# Relay_Board.net
KiCad netlist of a schematic drawn in EAGLE
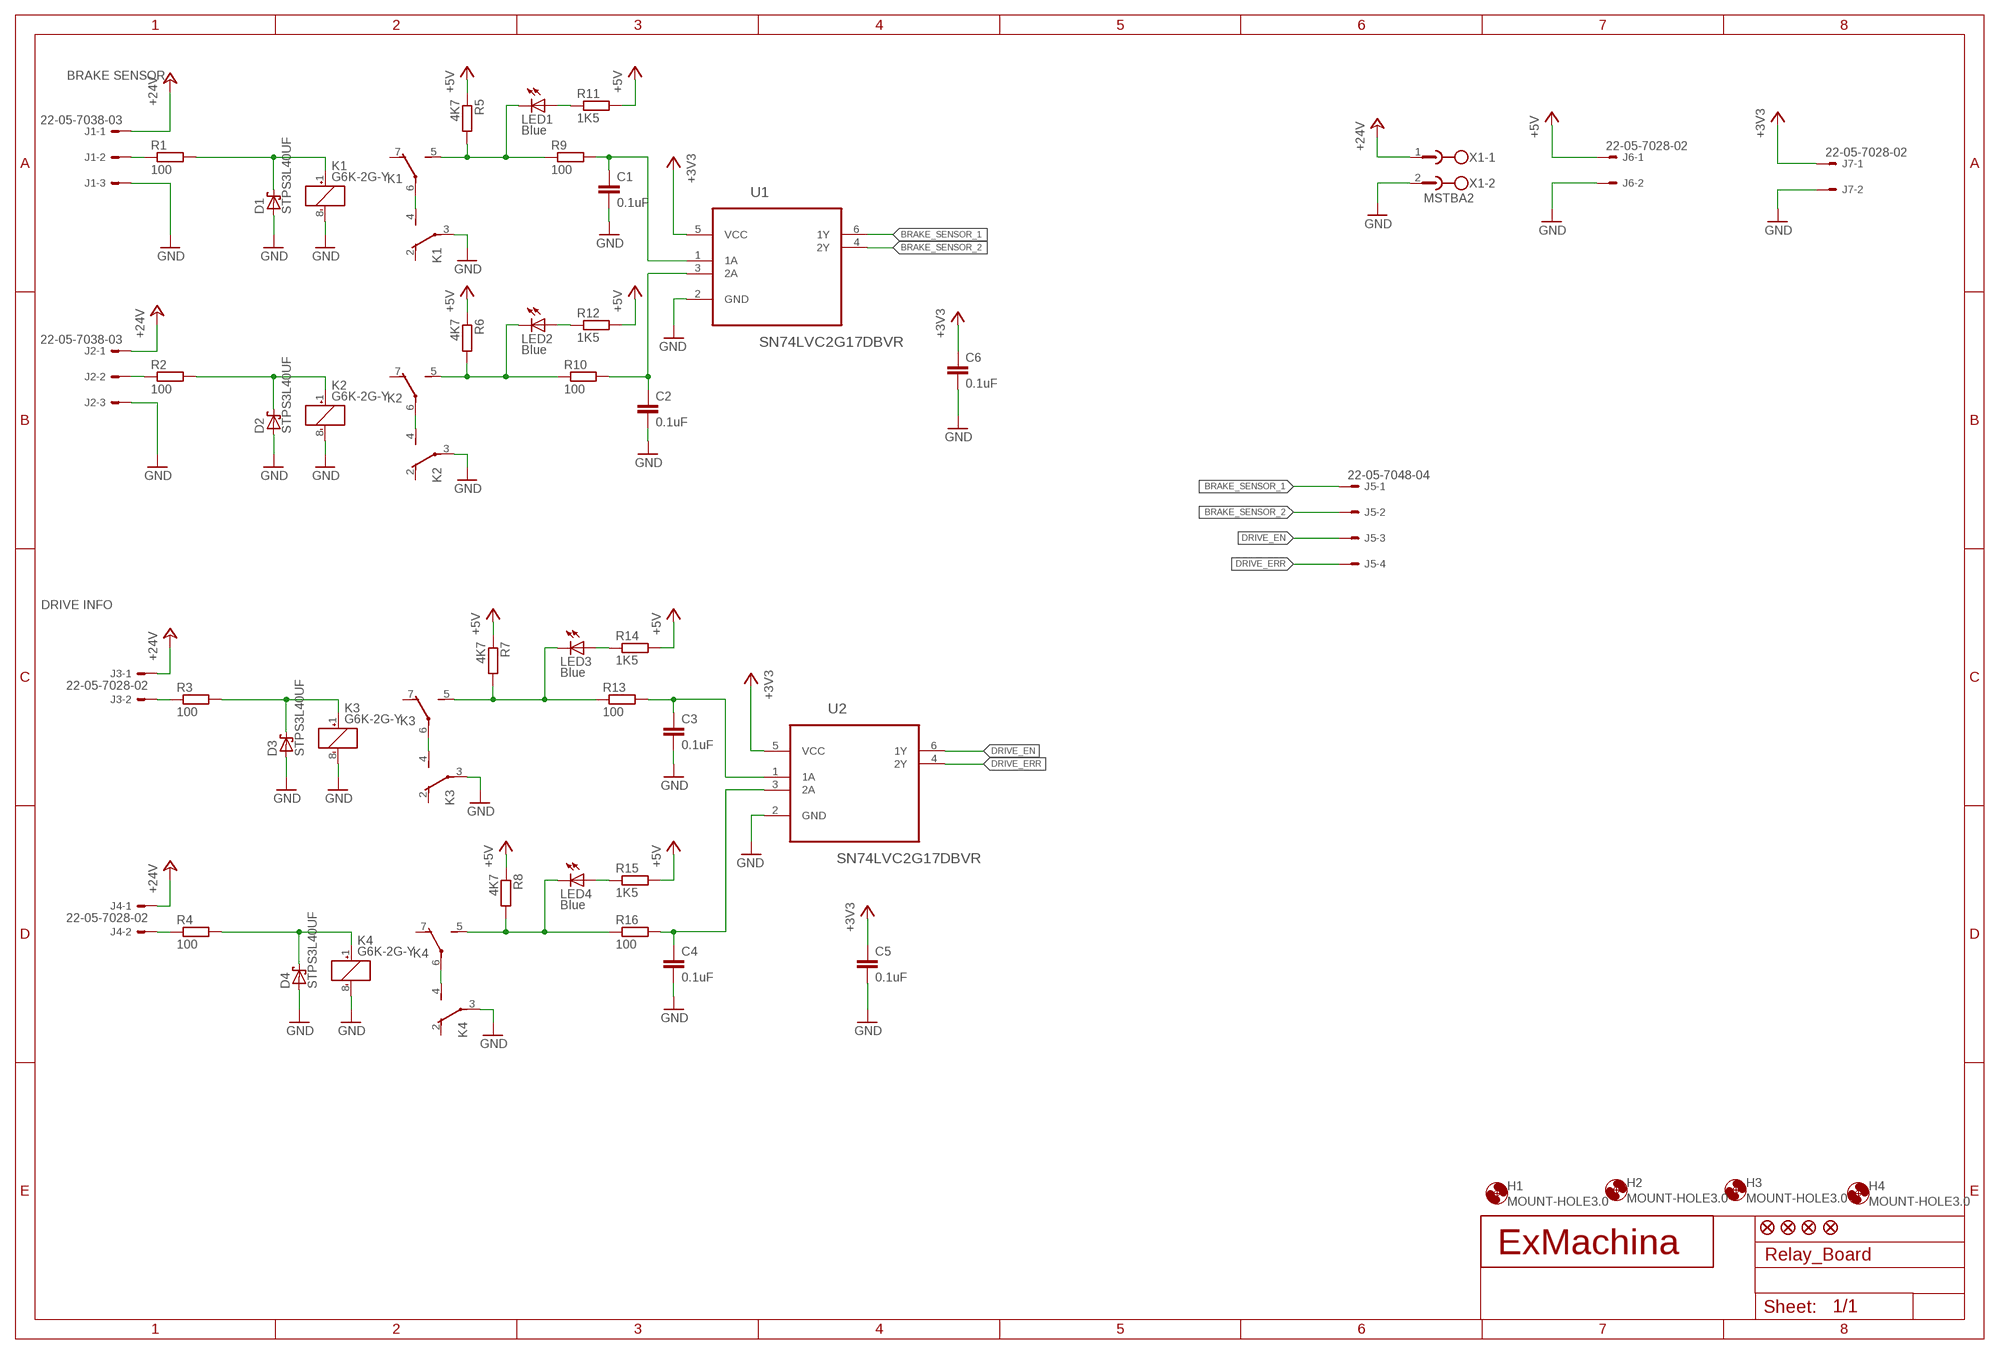
[diagram p0: schematic, sheet 1]

(export (version "E")
  (design (tool "Eeschema 10.0.6"))
  (components
    (comp (ref "C1")
      (value "0.1uF")
      (footprint "eagle-import:C0603")
      (fields (field (name "MPN") "MC0603B104K250CT"))
      (libsource (lib "eagle-import") (part "C-EUC0603"))
    )
    (comp (ref "C2")
      (value "0.1uF")
      (footprint "eagle-import:C0603")
      (fields (field (name "MPN") "MC0603B104K250CT"))
      (libsource (lib "eagle-import") (part "C-EUC0603"))
    )
    (comp (ref "C3")
      (value "0.1uF")
      (footprint "eagle-import:C0603")
      (fields (field (name "MPN") "MC0603B104K250CT"))
      (libsource (lib "eagle-import") (part "C-EUC0603"))
    )
    (comp (ref "C4")
      (value "0.1uF")
      (footprint "eagle-import:C0603")
      (fields (field (name "MPN") "MC0603B104K250CT"))
      (libsource (lib "eagle-import") (part "C-EUC0603"))
    )
    (comp (ref "C5")
      (value "0.1uF")
      (footprint "eagle-import:C0603")
      (fields (field (name "MPN") "MC0603B104K250CT"))
      (libsource (lib "eagle-import") (part "C-EUC0603"))
    )
    (comp (ref "C6")
      (value "0.1uF")
      (footprint "eagle-import:C0603")
      (fields (field (name "MPN") "MC0603B104K250CT"))
      (libsource (lib "eagle-import") (part "C-EUC0603"))
    )
    (comp (ref "D1")
      (value "STPS3L40UF")
      (footprint "eagle-import:SMB")
      (fields (field (name "MP") "STMICROELECTRONICS"))
      (libsource (lib "eagle-import") (part "STPS3L40?UF"))
    )
    (comp (ref "D2")
      (value "STPS3L40UF")
      (footprint "eagle-import:SMB")
      (fields (field (name "MP") "STMICROELECTRONICS"))
      (libsource (lib "eagle-import") (part "STPS3L40?UF"))
    )
    (comp (ref "D3")
      (value "STPS3L40UF")
      (footprint "eagle-import:SMB")
      (fields (field (name "MP") "STMICROELECTRONICS"))
      (libsource (lib "eagle-import") (part "STPS3L40?UF"))
    )
    (comp (ref "D4")
      (value "STPS3L40UF")
      (footprint "eagle-import:SMB")
      (fields (field (name "MP") "STMICROELECTRONICS"))
      (libsource (lib "eagle-import") (part "STPS3L40?UF"))
    )
    (comp (ref "H1")
      (value "MOUNT-HOLE3.0")
      (footprint "eagle-import:3,0")
      (libsource (lib "eagle-import") (part "MOUNT-HOLE3.0"))
    )
    (comp (ref "H2")
      (value "MOUNT-HOLE3.0")
      (footprint "eagle-import:3,0")
      (libsource (lib "eagle-import") (part "MOUNT-HOLE3.0"))
    )
    (comp (ref "H3")
      (value "MOUNT-HOLE3.0")
      (footprint "eagle-import:3,0")
      (libsource (lib "eagle-import") (part "MOUNT-HOLE3.0"))
    )
    (comp (ref "H4")
      (value "MOUNT-HOLE3.0")
      (footprint "eagle-import:3,0")
      (libsource (lib "eagle-import") (part "MOUNT-HOLE3.0"))
    )
    (comp (ref "J1")
      (value "22-05-7038-03")
      (footprint "eagle-import:7395-03")
      (fields (field (name "MPN") "22-05-7038") (field (name "OC_NEWARK") "26M6362"))
      (libsource (lib "eagle-import") (part "22-?-0305-7038"))
    )
    (comp (ref "J2")
      (value "22-05-7038-03")
      (footprint "eagle-import:7395-03")
      (fields (field (name "MPN") "22-05-7038") (field (name "OC_NEWARK") "26M6362"))
      (libsource (lib "eagle-import") (part "22-?-0305-7038"))
    )
    (comp (ref "J3")
      (value "22-05-7028-02")
      (footprint "eagle-import:7395-02")
      (fields (field (name "MPN") "22-05-7028") (field (name "OC_NEWARK") "25M1728"))
      (libsource (lib "eagle-import") (part "22-?-0205-7028"))
    )
    (comp (ref "J4")
      (value "22-05-7028-02")
      (footprint "eagle-import:7395-02")
      (fields (field (name "MPN") "22-05-7028") (field (name "OC_NEWARK") "25M1728"))
      (libsource (lib "eagle-import") (part "22-?-0205-7028"))
    )
    (comp (ref "J5")
      (value "22-05-7048-04")
      (footprint "eagle-import:7395-04")
      (fields (field (name "MPN") "22-05-7048") (field (name "OC_NEWARK") "26M6363"))
      (libsource (lib "eagle-import") (part "22-?-0405-7048"))
    )
    (comp (ref "J6")
      (value "22-05-7028-02")
      (footprint "eagle-import:7395-02")
      (fields (field (name "MPN") "22-05-7028") (field (name "OC_NEWARK") "25M1728"))
      (libsource (lib "eagle-import") (part "22-?-0205-7028"))
    )
    (comp (ref "J7")
      (value "22-05-7028-02")
      (footprint "eagle-import:7395-02")
      (fields (field (name "MPN") "22-05-7028") (field (name "OC_NEWARK") "25M1728"))
      (libsource (lib "eagle-import") (part "22-?-0205-7028"))
    )
    (comp (ref "JP1")
      (value "FIDUCIAL1X2")
      (footprint "eagle-import:FIDUCIAL-1X2")
      (libsource (lib "eagle-import") (part "FIDUCIAL1X2"))
    )
    (comp (ref "JP2")
      (value "FIDUCIAL1X2")
      (footprint "eagle-import:FIDUCIAL-1X2")
      (libsource (lib "eagle-import") (part "FIDUCIAL1X2"))
    )
    (comp (ref "JP3")
      (value "FIDUCIAL1X2")
      (footprint "eagle-import:FIDUCIAL-1X2")
      (libsource (lib "eagle-import") (part "FIDUCIAL1X2"))
    )
    (comp (ref "JP4")
      (value "FIDUCIAL1X2")
      (footprint "eagle-import:FIDUCIAL-1X2")
      (libsource (lib "eagle-import") (part "FIDUCIAL1X2"))
    )
    (comp (ref "K1")
      (value "G6K-2G-Y")
      (footprint "eagle-import:G6K-2G-Y")
      (fields (field (name "MPN") "G6K-2G-Y 24DC") (field (name "OC_NEWARK") "82T9378"))
      (libsource (lib "eagle-import") (part "G6K-2G-Y"))
    )
    (comp (ref "K2")
      (value "G6K-2G-Y")
      (footprint "eagle-import:G6K-2G-Y")
      (fields (field (name "MPN") "G6K-2G-Y 24DC") (field (name "OC_NEWARK") "82T9378"))
      (libsource (lib "eagle-import") (part "G6K-2G-Y"))
    )
    (comp (ref "K3")
      (value "G6K-2G-Y")
      (footprint "eagle-import:G6K-2G-Y")
      (fields (field (name "MPN") "G6K-2G-Y 24DC") (field (name "OC_NEWARK") "82T9378"))
      (libsource (lib "eagle-import") (part "G6K-2G-Y"))
    )
    (comp (ref "K4")
      (value "G6K-2G-Y")
      (footprint "eagle-import:G6K-2G-Y")
      (fields (field (name "MPN") "G6K-2G-Y 24DC") (field (name "OC_NEWARK") "82T9378"))
      (libsource (lib "eagle-import") (part "G6K-2G-Y"))
    )
    (comp (ref "LED1")
      (value "Blue")
      (footprint "eagle-import:CHIPLED_0603")
      (fields (field (name "MPN") "OVS-0603"))
      (libsource (lib "eagle-import") (part "LEDCHIPLED_0603"))
    )
    (comp (ref "LED2")
      (value "Blue")
      (footprint "eagle-import:CHIPLED_0603")
      (fields (field (name "MPN") "OVS-0603"))
      (libsource (lib "eagle-import") (part "LEDCHIPLED_0603"))
    )
    (comp (ref "LED3")
      (value "Blue")
      (footprint "eagle-import:CHIPLED_0603")
      (fields (field (name "MPN") "OVS-0603"))
      (libsource (lib "eagle-import") (part "LEDCHIPLED_0603"))
    )
    (comp (ref "LED4")
      (value "Blue")
      (footprint "eagle-import:CHIPLED_0603")
      (fields (field (name "MPN") "OVS-0603"))
      (libsource (lib "eagle-import") (part "LEDCHIPLED_0603"))
    )
    (comp (ref "R1")
      (value "100")
      (footprint "eagle-import:R0603")
      (fields (field (name "MPN") "MCMR06X1000FTL"))
      (libsource (lib "eagle-import") (part "R-EU_R0603"))
    )
    (comp (ref "R2")
      (value "100")
      (footprint "eagle-import:R0603")
      (fields (field (name "MPN") "MCMR06X1000FTL"))
      (libsource (lib "eagle-import") (part "R-EU_R0603"))
    )
    (comp (ref "R3")
      (value "100")
      (footprint "eagle-import:R0603")
      (fields (field (name "MPN") "MCMR06X1000FTL"))
      (libsource (lib "eagle-import") (part "R-EU_R0603"))
    )
    (comp (ref "R4")
      (value "100")
      (footprint "eagle-import:R0603")
      (fields (field (name "MPN") "MCMR06X1000FTL"))
      (libsource (lib "eagle-import") (part "R-EU_R0603"))
    )
    (comp (ref "R5")
      (value "4K7")
      (footprint "eagle-import:R0603")
      (fields (field (name "MPN") "MCMR06X4701FTL"))
      (libsource (lib "eagle-import") (part "R-EU_R0603"))
    )
    (comp (ref "R6")
      (value "4K7")
      (footprint "eagle-import:R0603")
      (fields (field (name "MPN") "MCMR06X4701FTL"))
      (libsource (lib "eagle-import") (part "R-EU_R0603"))
    )
    (comp (ref "R7")
      (value "4K7")
      (footprint "eagle-import:R0603")
      (fields (field (name "MPN") "MCMR06X4701FTL"))
      (libsource (lib "eagle-import") (part "R-EU_R0603"))
    )
    (comp (ref "R8")
      (value "4K7")
      (footprint "eagle-import:R0603")
      (fields (field (name "MPN") "MCMR06X4701FTL"))
      (libsource (lib "eagle-import") (part "R-EU_R0603"))
    )
    (comp (ref "R9")
      (value "100")
      (footprint "eagle-import:R0603")
      (fields (field (name "MPN") "MCMR06X1000FTL"))
      (libsource (lib "eagle-import") (part "R-EU_R0603"))
    )
    (comp (ref "R10")
      (value "100")
      (footprint "eagle-import:R0603")
      (fields (field (name "MPN") "MCMR06X1000FTL"))
      (libsource (lib "eagle-import") (part "R-EU_R0603"))
    )
    (comp (ref "R11")
      (value "1K5")
      (footprint "eagle-import:R0603")
      (fields (field (name "MPN") "MCMR06X1501FTL"))
      (libsource (lib "eagle-import") (part "R-EU_R0603"))
    )
    (comp (ref "R12")
      (value "1K5")
      (footprint "eagle-import:R0603")
      (fields (field (name "MPN") "MCMR06X1501FTL"))
      (libsource (lib "eagle-import") (part "R-EU_R0603"))
    )
    (comp (ref "R13")
      (value "100")
      (footprint "eagle-import:R0603")
      (fields (field (name "MPN") "MCMR06X1000FTL"))
      (libsource (lib "eagle-import") (part "R-EU_R0603"))
    )
    (comp (ref "R14")
      (value "1K5")
      (footprint "eagle-import:R0603")
      (fields (field (name "MPN") "MCMR06X1501FTL"))
      (libsource (lib "eagle-import") (part "R-EU_R0603"))
    )
    (comp (ref "R15")
      (value "1K5")
      (footprint "eagle-import:R0603")
      (fields (field (name "MPN") "MCMR06X1501FTL"))
      (libsource (lib "eagle-import") (part "R-EU_R0603"))
    )
    (comp (ref "R16")
      (value "100")
      (footprint "eagle-import:R0603")
      (fields (field (name "MPN") "MCMR06X1000FTL"))
      (libsource (lib "eagle-import") (part "R-EU_R0603"))
    )
    (comp (ref "T1")
      (value "EXMACHINA-LOGO-NAME")
      (footprint "eagle-import:EXM-LOGO-BASELINE")
      (libsource (lib "eagle-import") (part "EXMACHINA-LOGO-NAME"))
    )
    (comp (ref "U1")
      (value "SN74LVC2G17DBVR")
      (footprint "eagle-import:SOT95P280X145-6N")
      (fields (field (name "MF") "TEXAS INSTRUMENTS"))
      (libsource (lib "eagle-import") (part "SN74LVC2G17DBVR"))
    )
    (comp (ref "U2")
      (value "SN74LVC2G17DBVR")
      (footprint "eagle-import:SOT95P280X145-6N")
      (fields (field (name "MF") "TEXAS INSTRUMENTS"))
      (libsource (lib "eagle-import") (part "SN74LVC2G17DBVR"))
    )
    (comp (ref "X1")
      (value "MSTBA2")
      (footprint "eagle-import:MSTBA2")
      (fields (field (name "MF") "FARNELL") (field (name "MPN") "1757242"))
      (libsource (lib "eagle-import") (part "MSTBA2"))
    )
  )
  (nets
    (net (code "1") (name "+3V3") (class "Default")
      (node (ref "C5") (pin "1") (pinfunction "1_1") (pintype "passive"))
      (node (ref "C6") (pin "1") (pinfunction "1_1") (pintype "passive"))
      (node (ref "J7") (pin "1") (pinfunction "S_1") (pintype "passive"))
      (node (ref "U1") (pin "5") (pinfunction "VCC_5") (pintype "power_in"))
      (node (ref "U2") (pin "5") (pinfunction "VCC_5") (pintype "power_in"))
    )
    (net (code "2") (name "+5V") (class "Default")
      (node (ref "J6") (pin "1") (pinfunction "S_1") (pintype "passive"))
      (node (ref "R11") (pin "2") (pinfunction "2_2") (pintype "passive"))
      (node (ref "R12") (pin "2") (pinfunction "2_2") (pintype "passive"))
      (node (ref "R14") (pin "2") (pinfunction "2_2") (pintype "passive"))
      (node (ref "R15") (pin "2") (pinfunction "2_2") (pintype "passive"))
      (node (ref "R5") (pin "1") (pinfunction "1_1") (pintype "passive"))
      (node (ref "R6") (pin "1") (pinfunction "1_1") (pintype "passive"))
      (node (ref "R7") (pin "1") (pinfunction "1_1") (pintype "passive"))
      (node (ref "R8") (pin "1") (pinfunction "1_1") (pintype "passive"))
    )
    (net (code "3") (name "+24V") (class "Default")
      (node (ref "J1") (pin "1") (pinfunction "S_1") (pintype "passive"))
      (node (ref "J2") (pin "1") (pinfunction "S_1") (pintype "passive"))
      (node (ref "J3") (pin "1") (pinfunction "S_1") (pintype "passive"))
      (node (ref "J4") (pin "1") (pinfunction "S_1") (pintype "passive"))
      (node (ref "X1") (pin "1") (pinfunction "1_1") (pintype "passive"))
    )
    (net (code "4") (name "BRAKE_SENSOR_1") (class "Default")
      (node (ref "J5") (pin "1") (pinfunction "S_1") (pintype "passive"))
      (node (ref "U1") (pin "6") (pinfunction "1Y_6") (pintype "output"))
    )
    (net (code "5") (name "BRAKE_SENSOR_2") (class "Default")
      (node (ref "J5") (pin "2") (pinfunction "S_2") (pintype "passive"))
      (node (ref "U1") (pin "4") (pinfunction "2Y_4") (pintype "output"))
    )
    (net (code "6") (name "DRIVE_EN") (class "Default")
      (node (ref "J5") (pin "3") (pinfunction "S_3") (pintype "passive"))
      (node (ref "U2") (pin "6") (pinfunction "1Y_6") (pintype "output"))
    )
    (net (code "7") (name "DRIVE_ERR") (class "Default")
      (node (ref "J5") (pin "4") (pinfunction "S_4") (pintype "passive"))
      (node (ref "U2") (pin "4") (pinfunction "2Y_4") (pintype "output"))
    )
    (net (code "8") (name "GND") (class "Default")
      (node (ref "C1") (pin "2") (pinfunction "2_2") (pintype "passive"))
      (node (ref "C2") (pin "2") (pinfunction "2_2") (pintype "passive"))
      (node (ref "C3") (pin "2") (pinfunction "2_2") (pintype "passive"))
      (node (ref "C4") (pin "2") (pinfunction "2_2") (pintype "passive"))
      (node (ref "C5") (pin "2") (pinfunction "2_2") (pintype "passive"))
      (node (ref "C6") (pin "2") (pinfunction "2_2") (pintype "passive"))
      (node (ref "D1") (pin "A") (pinfunction "A_A") (pintype "passive"))
      (node (ref "D2") (pin "A") (pinfunction "A_A") (pintype "passive"))
      (node (ref "D3") (pin "A") (pinfunction "A_A") (pintype "passive"))
      (node (ref "D4") (pin "A") (pinfunction "A_A") (pintype "passive"))
      (node (ref "J1") (pin "3") (pinfunction "S_3") (pintype "passive"))
      (node (ref "J2") (pin "3") (pinfunction "S_3") (pintype "passive"))
      (node (ref "J6") (pin "2") (pinfunction "S_2") (pintype "passive"))
      (node (ref "J7") (pin "2") (pinfunction "S_2") (pintype "passive"))
      (node (ref "K1") (pin "3") (pinfunction "P_3") (pintype "passive"))
      (node (ref "K1") (pin "8") (pinfunction "-_8") (pintype "passive"))
      (node (ref "K2") (pin "3") (pinfunction "P_3") (pintype "passive"))
      (node (ref "K2") (pin "8") (pinfunction "-_8") (pintype "passive"))
      (node (ref "K3") (pin "3") (pinfunction "P_3") (pintype "passive"))
      (node (ref "K3") (pin "8") (pinfunction "-_8") (pintype "passive"))
      (node (ref "K4") (pin "3") (pinfunction "P_3") (pintype "passive"))
      (node (ref "K4") (pin "8") (pinfunction "-_8") (pintype "passive"))
      (node (ref "U1") (pin "2") (pinfunction "GND_2") (pintype "passive"))
      (node (ref "U2") (pin "2") (pinfunction "GND_2") (pintype "passive"))
      (node (ref "X1") (pin "2") (pinfunction "1_2") (pintype "passive"))
    )
    (net (code "9") (name "Net-(J1B-S)") (class "Default")
      (node (ref "J1") (pin "2") (pinfunction "S_2") (pintype "passive"))
      (node (ref "R1") (pin "1") (pinfunction "1_1") (pintype "passive"))
    )
    (net (code "10") (name "Net-(J2B-S)") (class "Default")
      (node (ref "J2") (pin "2") (pinfunction "S_2") (pintype "passive"))
      (node (ref "R2") (pin "1") (pinfunction "1_1") (pintype "passive"))
    )
    (net (code "11") (name "Net-(J3B-S)") (class "Default")
      (node (ref "J3") (pin "2") (pinfunction "S_2") (pintype "passive"))
      (node (ref "R3") (pin "1") (pinfunction "1_1") (pintype "passive"))
    )
    (net (code "12") (name "Net-(J4B-S)") (class "Default")
      (node (ref "J4") (pin "2") (pinfunction "S_2") (pintype "passive"))
      (node (ref "R4") (pin "1") (pinfunction "1_1") (pintype "passive"))
    )
    (net (code "13") (name "Net-(K1A-+)") (class "Default")
      (node (ref "D1") (pin "C") (pinfunction "C_C") (pintype "passive"))
      (node (ref "K1") (pin "1") (pinfunction "+_1") (pintype "passive"))
      (node (ref "R1") (pin "2") (pinfunction "2_2") (pintype "passive"))
    )
    (net (code "14") (name "Net-(K1B-S)") (class "Default")
      (node (ref "K1") (pin "4") (pinfunction "S_4") (pintype "passive"))
      (node (ref "K1") (pin "6") (pinfunction "P_6") (pintype "passive"))
    )
    (net (code "15") (name "Net-(K1C-S)") (class "Default")
      (node (ref "K1") (pin "5") (pinfunction "S_5") (pintype "passive"))
      (node (ref "LED1") (pin "C") (pinfunction "C_C") (pintype "passive"))
      (node (ref "R5") (pin "2") (pinfunction "2_2") (pintype "passive"))
      (node (ref "R9") (pin "1") (pinfunction "1_1") (pintype "passive"))
    )
    (net (code "16") (name "Net-(K2A-+)") (class "Default")
      (node (ref "D2") (pin "C") (pinfunction "C_C") (pintype "passive"))
      (node (ref "K2") (pin "1") (pinfunction "+_1") (pintype "passive"))
      (node (ref "R2") (pin "2") (pinfunction "2_2") (pintype "passive"))
    )
    (net (code "17") (name "Net-(K2B-S)") (class "Default")
      (node (ref "K2") (pin "4") (pinfunction "S_4") (pintype "passive"))
      (node (ref "K2") (pin "6") (pinfunction "P_6") (pintype "passive"))
    )
    (net (code "18") (name "Net-(K2C-S)") (class "Default")
      (node (ref "K2") (pin "5") (pinfunction "S_5") (pintype "passive"))
      (node (ref "LED2") (pin "C") (pinfunction "C_C") (pintype "passive"))
      (node (ref "R10") (pin "1") (pinfunction "1_1") (pintype "passive"))
      (node (ref "R6") (pin "2") (pinfunction "2_2") (pintype "passive"))
    )
    (net (code "19") (name "Net-(K3A-+)") (class "Default")
      (node (ref "D3") (pin "C") (pinfunction "C_C") (pintype "passive"))
      (node (ref "K3") (pin "1") (pinfunction "+_1") (pintype "passive"))
      (node (ref "R3") (pin "2") (pinfunction "2_2") (pintype "passive"))
    )
    (net (code "20") (name "Net-(K3B-S)") (class "Default")
      (node (ref "K3") (pin "4") (pinfunction "S_4") (pintype "passive"))
      (node (ref "K3") (pin "6") (pinfunction "P_6") (pintype "passive"))
    )
    (net (code "21") (name "Net-(K3C-S)") (class "Default")
      (node (ref "K3") (pin "5") (pinfunction "S_5") (pintype "passive"))
      (node (ref "LED3") (pin "C") (pinfunction "C_C") (pintype "passive"))
      (node (ref "R13") (pin "1") (pinfunction "1_1") (pintype "passive"))
      (node (ref "R7") (pin "2") (pinfunction "2_2") (pintype "passive"))
    )
    (net (code "22") (name "Net-(K4A-+)") (class "Default")
      (node (ref "D4") (pin "C") (pinfunction "C_C") (pintype "passive"))
      (node (ref "K4") (pin "1") (pinfunction "+_1") (pintype "passive"))
      (node (ref "R4") (pin "2") (pinfunction "2_2") (pintype "passive"))
    )
    (net (code "23") (name "Net-(K4B-S)") (class "Default")
      (node (ref "K4") (pin "4") (pinfunction "S_4") (pintype "passive"))
      (node (ref "K4") (pin "6") (pinfunction "P_6") (pintype "passive"))
    )
    (net (code "24") (name "Net-(K4C-S)") (class "Default")
      (node (ref "K4") (pin "5") (pinfunction "S_5") (pintype "passive"))
      (node (ref "LED4") (pin "C") (pinfunction "C_C") (pintype "passive"))
      (node (ref "R16") (pin "1") (pinfunction "1_1") (pintype "passive"))
      (node (ref "R8") (pin "2") (pinfunction "2_2") (pintype "passive"))
    )
    (net (code "25") (name "Net-(LED1-PadA)") (class "Default")
      (node (ref "LED1") (pin "A") (pinfunction "A_A") (pintype "passive"))
      (node (ref "R11") (pin "1") (pinfunction "1_1") (pintype "passive"))
    )
    (net (code "26") (name "Net-(LED2-PadA)") (class "Default")
      (node (ref "LED2") (pin "A") (pinfunction "A_A") (pintype "passive"))
      (node (ref "R12") (pin "1") (pinfunction "1_1") (pintype "passive"))
    )
    (net (code "27") (name "Net-(LED3-PadA)") (class "Default")
      (node (ref "LED3") (pin "A") (pinfunction "A_A") (pintype "passive"))
      (node (ref "R14") (pin "1") (pinfunction "1_1") (pintype "passive"))
    )
    (net (code "28") (name "Net-(LED4-PadA)") (class "Default")
      (node (ref "LED4") (pin "A") (pinfunction "A_A") (pintype "passive"))
      (node (ref "R15") (pin "1") (pinfunction "1_1") (pintype "passive"))
    )
    (net (code "29") (name "Net-(U1-1A)") (class "Default")
      (node (ref "C1") (pin "1") (pinfunction "1_1") (pintype "passive"))
      (node (ref "R9") (pin "2") (pinfunction "2_2") (pintype "passive"))
      (node (ref "U1") (pin "1") (pinfunction "1A_1") (pintype "input"))
    )
    (net (code "30") (name "Net-(U1-2A)") (class "Default")
      (node (ref "C2") (pin "1") (pinfunction "1_1") (pintype "passive"))
      (node (ref "R10") (pin "2") (pinfunction "2_2") (pintype "passive"))
      (node (ref "U1") (pin "3") (pinfunction "2A_3") (pintype "input"))
    )
    (net (code "31") (name "Net-(U2-1A)") (class "Default")
      (node (ref "C3") (pin "1") (pinfunction "1_1") (pintype "passive"))
      (node (ref "R13") (pin "2") (pinfunction "2_2") (pintype "passive"))
      (node (ref "U2") (pin "1") (pinfunction "1A_1") (pintype "input"))
    )
    (net (code "32") (name "Net-(U2-2A)") (class "Default")
      (node (ref "C4") (pin "1") (pinfunction "1_1") (pintype "passive"))
      (node (ref "R16") (pin "2") (pinfunction "2_2") (pintype "passive"))
      (node (ref "U2") (pin "3") (pinfunction "2A_3") (pintype "input"))
    )
    (net (code "33") (name "unconnected-(K1B-O-Pad2)") (class "Default")
      (node (ref "K1") (pin "2") (pinfunction "O_2") (pintype "passive"))
    )
    (net (code "34") (name "unconnected-(K1C-O-Pad7)") (class "Default")
      (node (ref "K1") (pin "7") (pinfunction "O_7") (pintype "passive"))
    )
    (net (code "35") (name "unconnected-(K2B-O-Pad2)") (class "Default")
      (node (ref "K2") (pin "2") (pinfunction "O_2") (pintype "passive"))
    )
    (net (code "36") (name "unconnected-(K2C-O-Pad7)") (class "Default")
      (node (ref "K2") (pin "7") (pinfunction "O_7") (pintype "passive"))
    )
    (net (code "37") (name "unconnected-(K3B-O-Pad2)") (class "Default")
      (node (ref "K3") (pin "2") (pinfunction "O_2") (pintype "passive"))
    )
    (net (code "38") (name "unconnected-(K3C-O-Pad7)") (class "Default")
      (node (ref "K3") (pin "7") (pinfunction "O_7") (pintype "passive"))
    )
    (net (code "39") (name "unconnected-(K4B-O-Pad2)") (class "Default")
      (node (ref "K4") (pin "2") (pinfunction "O_2") (pintype "passive"))
    )
    (net (code "40") (name "unconnected-(K4C-O-Pad7)") (class "Default")
      (node (ref "K4") (pin "7") (pinfunction "O_7") (pintype "passive"))
    )
  )
)
